# LED_Readout_and_Warning_Lights.net
KiCad netlist of a schematic drawn in Altium Designer
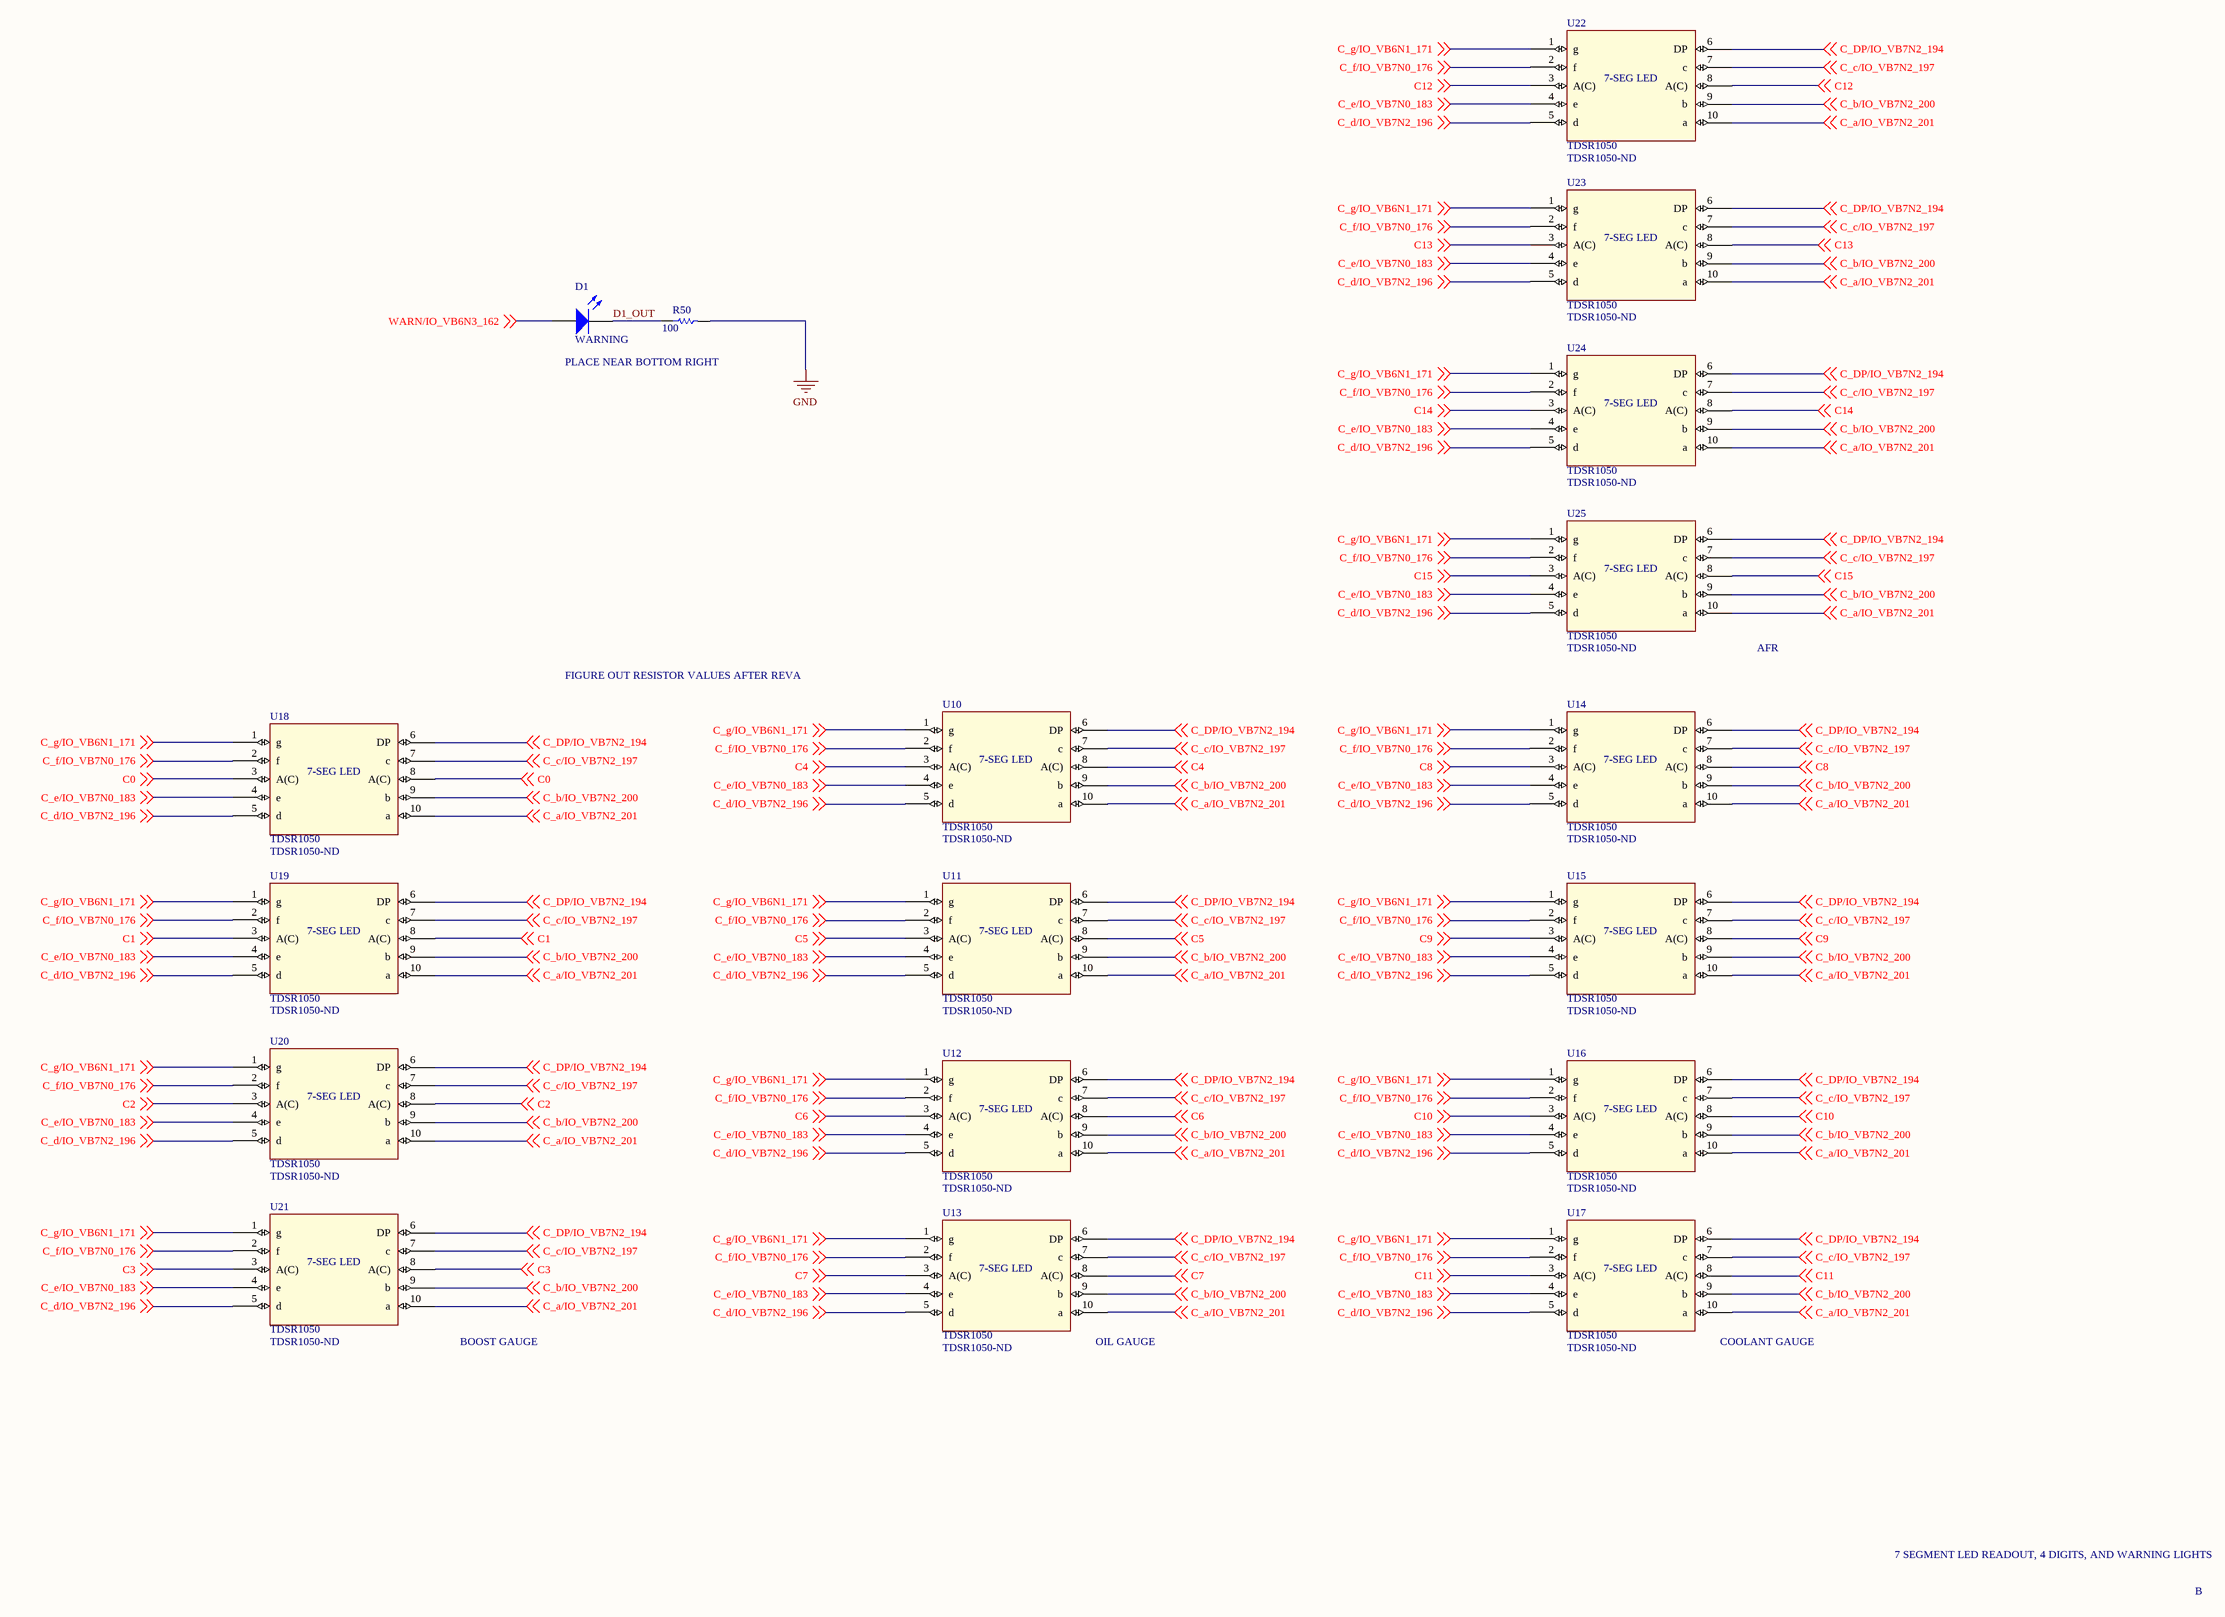
[diagram p0: LED_Readout_and_Warning_Lights.SchDoc]

(export (version "E")
  (design (tool "Eeschema 10.0.6"))
  (components
    (comp (ref "D1")
      (value "WARNING")
      (footprint "DIODE_0603")
      (description "Typical INFRARED GaAs LED")
      (fields (field (name "PUBLISHER") "Altium Limited"))
      (libsource (lib "Miscellaneous Devices") (part "LED0"))
    )
    (comp (ref "R50")
      (value "100")
      (footprint "RES_0603")
      (description "Resistor")
      (fields
        (field (name "Comment") "Figure out ohmage after RevA")
        (field (name "PUBLISHER") "Altium Limited")
      )
      (libsource (lib "Miscellaneous Devices") (part "Res1"))
    )
    (comp (ref "U10")
      (value "TDSR1050")
      (footprint "TDSR1050")
      (description "High Intensity Red Low Current 7-Segment Display")
      (fields (field (name "SUPPLIER PART NUMBER 1") "TDSR1050-ND"))
      (libsource (lib "schematics") (part "TDSR1050"))
    )
    (comp (ref "U11")
      (value "TDSR1050")
      (footprint "TDSR1050")
      (description "High Intensity Red Low Current 7-Segment Display")
      (fields (field (name "SUPPLIER PART NUMBER 1") "TDSR1050-ND"))
      (libsource (lib "schematics") (part "TDSR1050"))
    )
    (comp (ref "U12")
      (value "TDSR1050")
      (footprint "TDSR1050")
      (description "High Intensity Red Low Current 7-Segment Display")
      (fields (field (name "SUPPLIER PART NUMBER 1") "TDSR1050-ND"))
      (libsource (lib "schematics") (part "TDSR1050"))
    )
    (comp (ref "U13")
      (value "TDSR1050")
      (footprint "TDSR1050")
      (description "High Intensity Red Low Current 7-Segment Display")
      (fields (field (name "SUPPLIER PART NUMBER 1") "TDSR1050-ND"))
      (libsource (lib "schematics") (part "TDSR1050"))
    )
    (comp (ref "U14")
      (value "TDSR1050")
      (footprint "TDSR1050")
      (description "High Intensity Red Low Current 7-Segment Display")
      (fields (field (name "SUPPLIER PART NUMBER 1") "TDSR1050-ND"))
      (libsource (lib "schematics") (part "TDSR1050"))
    )
    (comp (ref "U15")
      (value "TDSR1050")
      (footprint "TDSR1050")
      (description "High Intensity Red Low Current 7-Segment Display")
      (fields (field (name "SUPPLIER PART NUMBER 1") "TDSR1050-ND"))
      (libsource (lib "schematics") (part "TDSR1050"))
    )
    (comp (ref "U16")
      (value "TDSR1050")
      (footprint "TDSR1050")
      (description "High Intensity Red Low Current 7-Segment Display")
      (fields (field (name "SUPPLIER PART NUMBER 1") "TDSR1050-ND"))
      (libsource (lib "schematics") (part "TDSR1050"))
    )
    (comp (ref "U17")
      (value "TDSR1050")
      (footprint "TDSR1050")
      (description "High Intensity Red Low Current 7-Segment Display")
      (fields (field (name "SUPPLIER PART NUMBER 1") "TDSR1050-ND"))
      (libsource (lib "schematics") (part "TDSR1050"))
    )
    (comp (ref "U18")
      (value "TDSR1050")
      (footprint "TDSR1050")
      (description "High Intensity Red Low Current 7-Segment Display")
      (fields (field (name "SUPPLIER PART NUMBER 1") "TDSR1050-ND"))
      (libsource (lib "schematics") (part "TDSR1050"))
    )
    (comp (ref "U19")
      (value "TDSR1050")
      (footprint "TDSR1050")
      (description "High Intensity Red Low Current 7-Segment Display")
      (fields (field (name "SUPPLIER PART NUMBER 1") "TDSR1050-ND"))
      (libsource (lib "schematics") (part "TDSR1050"))
    )
    (comp (ref "U20")
      (value "TDSR1050")
      (footprint "TDSR1050")
      (description "High Intensity Red Low Current 7-Segment Display")
      (fields (field (name "SUPPLIER PART NUMBER 1") "TDSR1050-ND"))
      (libsource (lib "schematics") (part "TDSR1050"))
    )
    (comp (ref "U21")
      (value "TDSR1050")
      (footprint "TDSR1050")
      (description "High Intensity Red Low Current 7-Segment Display")
      (fields (field (name "SUPPLIER PART NUMBER 1") "TDSR1050-ND"))
      (libsource (lib "schematics") (part "TDSR1050"))
    )
    (comp (ref "U22")
      (value "TDSR1050")
      (footprint "TDSR1050")
      (description "High Intensity Red Low Current 7-Segment Display")
      (fields (field (name "SUPPLIER PART NUMBER 1") "TDSR1050-ND"))
      (libsource (lib "schematics") (part "TDSR1050"))
    )
    (comp (ref "U23")
      (value "TDSR1050")
      (footprint "TDSR1050")
      (description "High Intensity Red Low Current 7-Segment Display")
      (fields (field (name "SUPPLIER PART NUMBER 1") "TDSR1050-ND"))
      (libsource (lib "schematics") (part "TDSR1050"))
    )
    (comp (ref "U24")
      (value "TDSR1050")
      (footprint "TDSR1050")
      (description "High Intensity Red Low Current 7-Segment Display")
      (fields (field (name "SUPPLIER PART NUMBER 1") "TDSR1050-ND"))
      (libsource (lib "schematics") (part "TDSR1050"))
    )
    (comp (ref "U25")
      (value "TDSR1050")
      (footprint "TDSR1050")
      (description "High Intensity Red Low Current 7-Segment Display")
      (fields (field (name "SUPPLIER PART NUMBER 1") "TDSR1050-ND"))
      (libsource (lib "schematics") (part "TDSR1050"))
    )
  )
  (nets
    (net (code "1") (name "/D1_OUT") (class "Default")
      (node (ref "D1") (pin "2") (pinfunction "K_2") (pintype "passive"))
      (node (ref "R50") (pin "1") (pinfunction "1_1") (pintype "passive"))
    )
    (net (code "2") (name "C0") (class "Default")
      (node (ref "U18") (pin "3") (pinfunction "A(C)_3") (pintype "bidirectional"))
      (node (ref "U18") (pin "8") (pinfunction "A(C)_8") (pintype "bidirectional"))
    )
    (net (code "3") (name "C1") (class "Default")
      (node (ref "U19") (pin "3") (pinfunction "A(C)_3") (pintype "bidirectional"))
      (node (ref "U19") (pin "8") (pinfunction "A(C)_8") (pintype "bidirectional"))
    )
    (net (code "4") (name "C2") (class "Default")
      (node (ref "U20") (pin "3") (pinfunction "A(C)_3") (pintype "bidirectional"))
      (node (ref "U20") (pin "8") (pinfunction "A(C)_8") (pintype "bidirectional"))
    )
    (net (code "5") (name "C3") (class "Default")
      (node (ref "U21") (pin "3") (pinfunction "A(C)_3") (pintype "bidirectional"))
      (node (ref "U21") (pin "8") (pinfunction "A(C)_8") (pintype "bidirectional"))
    )
    (net (code "6") (name "C4") (class "Default")
      (node (ref "U10") (pin "3") (pinfunction "A(C)_3") (pintype "bidirectional"))
      (node (ref "U10") (pin "8") (pinfunction "A(C)_8") (pintype "bidirectional"))
    )
    (net (code "7") (name "C5") (class "Default")
      (node (ref "U11") (pin "3") (pinfunction "A(C)_3") (pintype "bidirectional"))
      (node (ref "U11") (pin "8") (pinfunction "A(C)_8") (pintype "bidirectional"))
    )
    (net (code "8") (name "C6") (class "Default")
      (node (ref "U12") (pin "3") (pinfunction "A(C)_3") (pintype "bidirectional"))
      (node (ref "U12") (pin "8") (pinfunction "A(C)_8") (pintype "bidirectional"))
    )
    (net (code "9") (name "C7") (class "Default")
      (node (ref "U13") (pin "3") (pinfunction "A(C)_3") (pintype "bidirectional"))
      (node (ref "U13") (pin "8") (pinfunction "A(C)_8") (pintype "bidirectional"))
    )
    (net (code "10") (name "C8") (class "Default")
      (node (ref "U14") (pin "3") (pinfunction "A(C)_3") (pintype "bidirectional"))
      (node (ref "U14") (pin "8") (pinfunction "A(C)_8") (pintype "bidirectional"))
    )
    (net (code "11") (name "C9") (class "Default")
      (node (ref "U15") (pin "3") (pinfunction "A(C)_3") (pintype "bidirectional"))
      (node (ref "U15") (pin "8") (pinfunction "A(C)_8") (pintype "bidirectional"))
    )
    (net (code "12") (name "C10") (class "Default")
      (node (ref "U16") (pin "3") (pinfunction "A(C)_3") (pintype "bidirectional"))
      (node (ref "U16") (pin "8") (pinfunction "A(C)_8") (pintype "bidirectional"))
    )
    (net (code "13") (name "C11") (class "Default")
      (node (ref "U17") (pin "3") (pinfunction "A(C)_3") (pintype "bidirectional"))
      (node (ref "U17") (pin "8") (pinfunction "A(C)_8") (pintype "bidirectional"))
    )
    (net (code "14") (name "C12") (class "Default")
      (node (ref "U22") (pin "3") (pinfunction "A(C)_3") (pintype "bidirectional"))
      (node (ref "U22") (pin "8") (pinfunction "A(C)_8") (pintype "bidirectional"))
    )
    (net (code "15") (name "C13") (class "Default")
      (node (ref "U23") (pin "3") (pinfunction "A(C)_3") (pintype "bidirectional"))
      (node (ref "U23") (pin "8") (pinfunction "A(C)_8") (pintype "bidirectional"))
    )
    (net (code "16") (name "C14") (class "Default")
      (node (ref "U24") (pin "3") (pinfunction "A(C)_3") (pintype "bidirectional"))
      (node (ref "U24") (pin "8") (pinfunction "A(C)_8") (pintype "bidirectional"))
    )
    (net (code "17") (name "C15") (class "Default")
      (node (ref "U25") (pin "3") (pinfunction "A(C)_3") (pintype "bidirectional"))
      (node (ref "U25") (pin "8") (pinfunction "A(C)_8") (pintype "bidirectional"))
    )
    (net (code "18") (name "C_DP{slash}IO_VB7N2_194") (class "Default")
      (node (ref "U10") (pin "6") (pinfunction "DP_6") (pintype "bidirectional"))
      (node (ref "U11") (pin "6") (pinfunction "DP_6") (pintype "bidirectional"))
      (node (ref "U12") (pin "6") (pinfunction "DP_6") (pintype "bidirectional"))
      (node (ref "U13") (pin "6") (pinfunction "DP_6") (pintype "bidirectional"))
      (node (ref "U14") (pin "6") (pinfunction "DP_6") (pintype "bidirectional"))
      (node (ref "U15") (pin "6") (pinfunction "DP_6") (pintype "bidirectional"))
      (node (ref "U16") (pin "6") (pinfunction "DP_6") (pintype "bidirectional"))
      (node (ref "U17") (pin "6") (pinfunction "DP_6") (pintype "bidirectional"))
      (node (ref "U18") (pin "6") (pinfunction "DP_6") (pintype "bidirectional"))
      (node (ref "U19") (pin "6") (pinfunction "DP_6") (pintype "bidirectional"))
      (node (ref "U20") (pin "6") (pinfunction "DP_6") (pintype "bidirectional"))
      (node (ref "U21") (pin "6") (pinfunction "DP_6") (pintype "bidirectional"))
      (node (ref "U22") (pin "6") (pinfunction "DP_6") (pintype "bidirectional"))
      (node (ref "U23") (pin "6") (pinfunction "DP_6") (pintype "bidirectional"))
      (node (ref "U24") (pin "6") (pinfunction "DP_6") (pintype "bidirectional"))
      (node (ref "U25") (pin "6") (pinfunction "DP_6") (pintype "bidirectional"))
    )
    (net (code "19") (name "C_a{slash}IO_VB7N2_201") (class "Default")
      (node (ref "U10") (pin "10") (pinfunction "a_10") (pintype "bidirectional"))
      (node (ref "U11") (pin "10") (pinfunction "a_10") (pintype "bidirectional"))
      (node (ref "U12") (pin "10") (pinfunction "a_10") (pintype "bidirectional"))
      (node (ref "U13") (pin "10") (pinfunction "a_10") (pintype "bidirectional"))
      (node (ref "U14") (pin "10") (pinfunction "a_10") (pintype "bidirectional"))
      (node (ref "U15") (pin "10") (pinfunction "a_10") (pintype "bidirectional"))
      (node (ref "U16") (pin "10") (pinfunction "a_10") (pintype "bidirectional"))
      (node (ref "U17") (pin "10") (pinfunction "a_10") (pintype "bidirectional"))
      (node (ref "U18") (pin "10") (pinfunction "a_10") (pintype "bidirectional"))
      (node (ref "U19") (pin "10") (pinfunction "a_10") (pintype "bidirectional"))
      (node (ref "U20") (pin "10") (pinfunction "a_10") (pintype "bidirectional"))
      (node (ref "U21") (pin "10") (pinfunction "a_10") (pintype "bidirectional"))
      (node (ref "U22") (pin "10") (pinfunction "a_10") (pintype "bidirectional"))
      (node (ref "U23") (pin "10") (pinfunction "a_10") (pintype "bidirectional"))
      (node (ref "U24") (pin "10") (pinfunction "a_10") (pintype "bidirectional"))
      (node (ref "U25") (pin "10") (pinfunction "a_10") (pintype "bidirectional"))
    )
    (net (code "20") (name "C_b{slash}IO_VB7N2_200") (class "Default")
      (node (ref "U10") (pin "9") (pinfunction "b_9") (pintype "bidirectional"))
      (node (ref "U11") (pin "9") (pinfunction "b_9") (pintype "bidirectional"))
      (node (ref "U12") (pin "9") (pinfunction "b_9") (pintype "bidirectional"))
      (node (ref "U13") (pin "9") (pinfunction "b_9") (pintype "bidirectional"))
      (node (ref "U14") (pin "9") (pinfunction "b_9") (pintype "bidirectional"))
      (node (ref "U15") (pin "9") (pinfunction "b_9") (pintype "bidirectional"))
      (node (ref "U16") (pin "9") (pinfunction "b_9") (pintype "bidirectional"))
      (node (ref "U17") (pin "9") (pinfunction "b_9") (pintype "bidirectional"))
      (node (ref "U18") (pin "9") (pinfunction "b_9") (pintype "bidirectional"))
      (node (ref "U19") (pin "9") (pinfunction "b_9") (pintype "bidirectional"))
      (node (ref "U20") (pin "9") (pinfunction "b_9") (pintype "bidirectional"))
      (node (ref "U21") (pin "9") (pinfunction "b_9") (pintype "bidirectional"))
      (node (ref "U22") (pin "9") (pinfunction "b_9") (pintype "bidirectional"))
      (node (ref "U23") (pin "9") (pinfunction "b_9") (pintype "bidirectional"))
      (node (ref "U24") (pin "9") (pinfunction "b_9") (pintype "bidirectional"))
      (node (ref "U25") (pin "9") (pinfunction "b_9") (pintype "bidirectional"))
    )
    (net (code "21") (name "C_c{slash}IO_VB7N2_197") (class "Default")
      (node (ref "U10") (pin "7") (pinfunction "c_7") (pintype "bidirectional"))
      (node (ref "U11") (pin "7") (pinfunction "c_7") (pintype "bidirectional"))
      (node (ref "U12") (pin "7") (pinfunction "c_7") (pintype "bidirectional"))
      (node (ref "U13") (pin "7") (pinfunction "c_7") (pintype "bidirectional"))
      (node (ref "U14") (pin "7") (pinfunction "c_7") (pintype "bidirectional"))
      (node (ref "U15") (pin "7") (pinfunction "c_7") (pintype "bidirectional"))
      (node (ref "U16") (pin "7") (pinfunction "c_7") (pintype "bidirectional"))
      (node (ref "U17") (pin "7") (pinfunction "c_7") (pintype "bidirectional"))
      (node (ref "U18") (pin "7") (pinfunction "c_7") (pintype "bidirectional"))
      (node (ref "U19") (pin "7") (pinfunction "c_7") (pintype "bidirectional"))
      (node (ref "U20") (pin "7") (pinfunction "c_7") (pintype "bidirectional"))
      (node (ref "U21") (pin "7") (pinfunction "c_7") (pintype "bidirectional"))
      (node (ref "U22") (pin "7") (pinfunction "c_7") (pintype "bidirectional"))
      (node (ref "U23") (pin "7") (pinfunction "c_7") (pintype "bidirectional"))
      (node (ref "U24") (pin "7") (pinfunction "c_7") (pintype "bidirectional"))
      (node (ref "U25") (pin "7") (pinfunction "c_7") (pintype "bidirectional"))
    )
    (net (code "22") (name "C_d{slash}IO_VB7N2_196") (class "Default")
      (node (ref "U10") (pin "5") (pinfunction "d_5") (pintype "bidirectional"))
      (node (ref "U11") (pin "5") (pinfunction "d_5") (pintype "bidirectional"))
      (node (ref "U12") (pin "5") (pinfunction "d_5") (pintype "bidirectional"))
      (node (ref "U13") (pin "5") (pinfunction "d_5") (pintype "bidirectional"))
      (node (ref "U14") (pin "5") (pinfunction "d_5") (pintype "bidirectional"))
      (node (ref "U15") (pin "5") (pinfunction "d_5") (pintype "bidirectional"))
      (node (ref "U16") (pin "5") (pinfunction "d_5") (pintype "bidirectional"))
      (node (ref "U17") (pin "5") (pinfunction "d_5") (pintype "bidirectional"))
      (node (ref "U18") (pin "5") (pinfunction "d_5") (pintype "bidirectional"))
      (node (ref "U19") (pin "5") (pinfunction "d_5") (pintype "bidirectional"))
      (node (ref "U20") (pin "5") (pinfunction "d_5") (pintype "bidirectional"))
      (node (ref "U21") (pin "5") (pinfunction "d_5") (pintype "bidirectional"))
      (node (ref "U22") (pin "5") (pinfunction "d_5") (pintype "bidirectional"))
      (node (ref "U23") (pin "5") (pinfunction "d_5") (pintype "bidirectional"))
      (node (ref "U24") (pin "5") (pinfunction "d_5") (pintype "bidirectional"))
      (node (ref "U25") (pin "5") (pinfunction "d_5") (pintype "bidirectional"))
    )
    (net (code "23") (name "C_e{slash}IO_VB7N0_183") (class "Default")
      (node (ref "U10") (pin "4") (pinfunction "e_4") (pintype "bidirectional"))
      (node (ref "U11") (pin "4") (pinfunction "e_4") (pintype "bidirectional"))
      (node (ref "U12") (pin "4") (pinfunction "e_4") (pintype "bidirectional"))
      (node (ref "U13") (pin "4") (pinfunction "e_4") (pintype "bidirectional"))
      (node (ref "U14") (pin "4") (pinfunction "e_4") (pintype "bidirectional"))
      (node (ref "U15") (pin "4") (pinfunction "e_4") (pintype "bidirectional"))
      (node (ref "U16") (pin "4") (pinfunction "e_4") (pintype "bidirectional"))
      (node (ref "U17") (pin "4") (pinfunction "e_4") (pintype "bidirectional"))
      (node (ref "U18") (pin "4") (pinfunction "e_4") (pintype "bidirectional"))
      (node (ref "U19") (pin "4") (pinfunction "e_4") (pintype "bidirectional"))
      (node (ref "U20") (pin "4") (pinfunction "e_4") (pintype "bidirectional"))
      (node (ref "U21") (pin "4") (pinfunction "e_4") (pintype "bidirectional"))
      (node (ref "U22") (pin "4") (pinfunction "e_4") (pintype "bidirectional"))
      (node (ref "U23") (pin "4") (pinfunction "e_4") (pintype "bidirectional"))
      (node (ref "U24") (pin "4") (pinfunction "e_4") (pintype "bidirectional"))
      (node (ref "U25") (pin "4") (pinfunction "e_4") (pintype "bidirectional"))
    )
    (net (code "24") (name "C_f{slash}IO_VB7N0_176") (class "Default")
      (node (ref "U10") (pin "2") (pinfunction "f_2") (pintype "bidirectional"))
      (node (ref "U11") (pin "2") (pinfunction "f_2") (pintype "bidirectional"))
      (node (ref "U12") (pin "2") (pinfunction "f_2") (pintype "bidirectional"))
      (node (ref "U13") (pin "2") (pinfunction "f_2") (pintype "bidirectional"))
      (node (ref "U14") (pin "2") (pinfunction "f_2") (pintype "bidirectional"))
      (node (ref "U15") (pin "2") (pinfunction "f_2") (pintype "bidirectional"))
      (node (ref "U16") (pin "2") (pinfunction "f_2") (pintype "bidirectional"))
      (node (ref "U17") (pin "2") (pinfunction "f_2") (pintype "bidirectional"))
      (node (ref "U18") (pin "2") (pinfunction "f_2") (pintype "bidirectional"))
      (node (ref "U19") (pin "2") (pinfunction "f_2") (pintype "bidirectional"))
      (node (ref "U20") (pin "2") (pinfunction "f_2") (pintype "bidirectional"))
      (node (ref "U21") (pin "2") (pinfunction "f_2") (pintype "bidirectional"))
      (node (ref "U22") (pin "2") (pinfunction "f_2") (pintype "bidirectional"))
      (node (ref "U23") (pin "2") (pinfunction "f_2") (pintype "bidirectional"))
      (node (ref "U24") (pin "2") (pinfunction "f_2") (pintype "bidirectional"))
      (node (ref "U25") (pin "2") (pinfunction "f_2") (pintype "bidirectional"))
    )
    (net (code "25") (name "C_g{slash}IO_VB6N1_171") (class "Default")
      (node (ref "U10") (pin "1") (pinfunction "g_1") (pintype "bidirectional"))
      (node (ref "U11") (pin "1") (pinfunction "g_1") (pintype "bidirectional"))
      (node (ref "U12") (pin "1") (pinfunction "g_1") (pintype "bidirectional"))
      (node (ref "U13") (pin "1") (pinfunction "g_1") (pintype "bidirectional"))
      (node (ref "U14") (pin "1") (pinfunction "g_1") (pintype "bidirectional"))
      (node (ref "U15") (pin "1") (pinfunction "g_1") (pintype "bidirectional"))
      (node (ref "U16") (pin "1") (pinfunction "g_1") (pintype "bidirectional"))
      (node (ref "U17") (pin "1") (pinfunction "g_1") (pintype "bidirectional"))
      (node (ref "U18") (pin "1") (pinfunction "g_1") (pintype "bidirectional"))
      (node (ref "U19") (pin "1") (pinfunction "g_1") (pintype "bidirectional"))
      (node (ref "U20") (pin "1") (pinfunction "g_1") (pintype "bidirectional"))
      (node (ref "U21") (pin "1") (pinfunction "g_1") (pintype "bidirectional"))
      (node (ref "U22") (pin "1") (pinfunction "g_1") (pintype "bidirectional"))
      (node (ref "U23") (pin "1") (pinfunction "g_1") (pintype "bidirectional"))
      (node (ref "U24") (pin "1") (pinfunction "g_1") (pintype "bidirectional"))
      (node (ref "U25") (pin "1") (pinfunction "g_1") (pintype "bidirectional"))
    )
    (net (code "26") (name "GND") (class "Default")
      (node (ref "R50") (pin "2") (pinfunction "2_2") (pintype "passive"))
    )
    (net (code "27") (name "WARN{slash}IO_VB6N3_162") (class "Default")
      (node (ref "D1") (pin "1") (pinfunction "A_1") (pintype "passive"))
    )
  )
)
